# power.net
KiCad netlist of a schematic drawn in Altium Designer
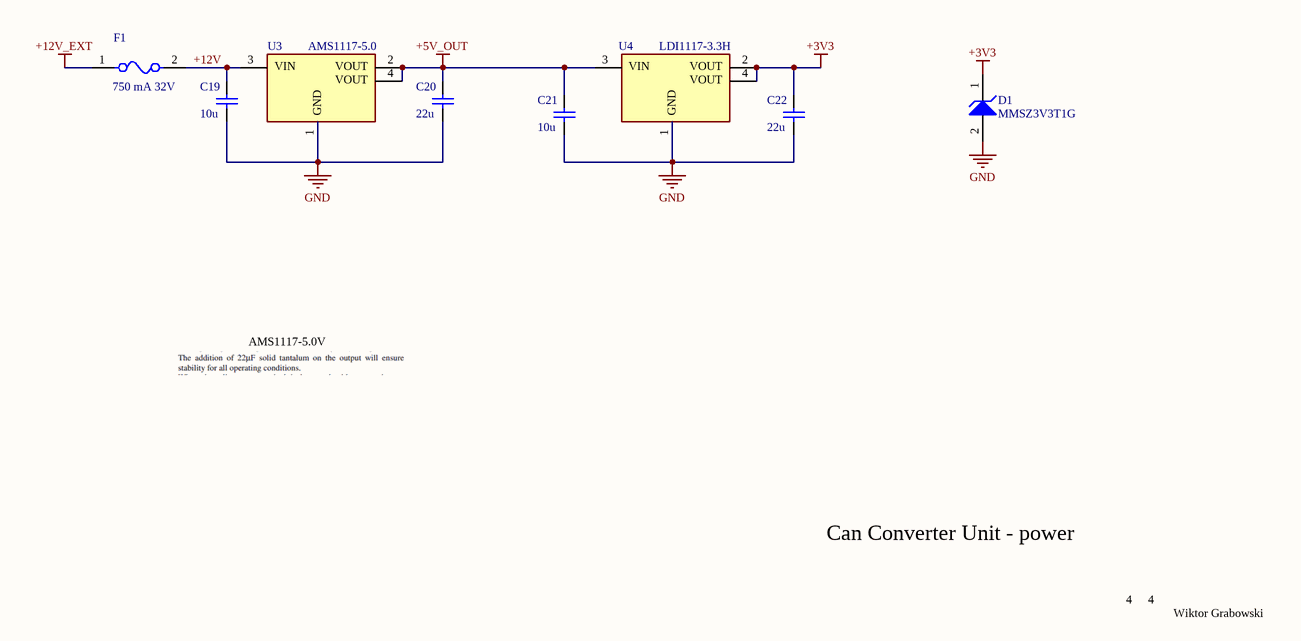
[diagram p0: power.SchDoc]

(export (version "E")
  (design (tool "Eeschema 10.0.6"))
  (components
    (comp (ref "C19")
      (value "10u")
      (footprint "CAPC1206(3216)170_M")
      (description "CAP 47nF 200V ±10% 1206 (3216 Metric) Thickness 1.7mm SMD")
      (fields (field (name "TOLERANCE") "Â±10%"))
      (libsource (lib "Altium Content Vault") (part "CAP"))
    )
    (comp (ref "C20")
      (value "22u")
      (footprint "CAPC1206(3216)170_M")
      (description "CAP 47nF 200V ±10% 1206 (3216 Metric) Thickness 1.7mm SMD")
      (fields (field (name "TOLERANCE") "Â±10%"))
      (libsource (lib "Altium Content Vault") (part "CAP"))
    )
    (comp (ref "C21")
      (value "10u")
      (footprint "CAPC1206(3216)170_M")
      (description "CAP 47nF 200V ±10% 1206 (3216 Metric) Thickness 1.7mm SMD")
      (fields (field (name "TOLERANCE") "Â±10%"))
      (libsource (lib "Altium Content Vault") (part "CAP"))
    )
    (comp (ref "C22")
      (value "22u")
      (footprint "CAPC1206(3216)170_M")
      (description "CAP 47nF 200V ±10% 1206 (3216 Metric) Thickness 1.7mm SMD")
      (fields (field (name "TOLERANCE") "Â±10%"))
      (libsource (lib "Altium Content Vault") (part "CAP"))
    )
    (comp (ref "D1")
      (value "MMSZ3V3T1G")
      (footprint "ONSC-SOD-123-2-425-04_V")
      (description "Zener Voltage Regulator, 500 mW, 2-Pin SOD-123, Pb-Free, Tape and Reel")
      (fields (field (name "MANUFACTURER") "On Semiconductor"))
      (libsource (lib "Altium Content Vault") (part "ONSC-K1A2-2"))
    )
    (comp (ref "F1")
      (value "750 mA 32V")
      (footprint "FP-0466-MFG")
      (description "FUSE BOARD MOUNT 750MA 63VAC/VDC")
      (libsource (lib "Altium Content Vault") (part "5bcf9b9f640e542cf0359d10258e979"))
    )
    (comp (ref "U3")
      (value "AMS1117-5.0")
      (footprint "AMS1117-5.0")
      (description "1A LOW DROPOUT VOLTAGE REGULATOR")
      (libsource (lib "HydrogreenLibrary") (part "AMS1117-5.0"))
    )
    (comp (ref "U4")
      (value "LDI1117-3.3H")
      (footprint "LDI1117-3.3H")
      (description "Fixed Positive LDO Regulator")
      (fields (field (name "MANUFACTURER") "Diotec"))
      (libsource (lib "HydrogreenLibrary") (part "LDI1117-3.3H"))
    )
  )
  (nets
    (net (code "1") (name "+3V3") (class "Default")
      (node (ref "C22") (pin "2") (pinfunction "2_2") (pintype "passive"))
      (node (ref "D1") (pin "1") (pinfunction "K_1") (pintype "passive"))
      (node (ref "U4") (pin "2") (pintype "power_in"))
      (node (ref "U4") (pin "4") (pintype "power_in"))
    )
    (net (code "2") (name "+5V_OUT") (class "Default")
      (node (ref "C20") (pin "2") (pinfunction "2_2") (pintype "passive"))
      (node (ref "C21") (pin "2") (pinfunction "2_2") (pintype "passive"))
      (node (ref "U3") (pin "2") (pintype "power_in"))
      (node (ref "U3") (pin "4") (pintype "power_in"))
      (node (ref "U4") (pin "3") (pintype "power_in"))
    )
    (net (code "3") (name "+12V_EXT") (class "Default")
      (node (ref "F1") (pin "1") (pinfunction "1_1") (pintype "passive"))
    )
    (net (code "4") (name "/+12V") (class "Default")
      (node (ref "C19") (pin "2") (pinfunction "2_2") (pintype "passive"))
      (node (ref "F1") (pin "2") (pinfunction "2_2") (pintype "passive"))
      (node (ref "U3") (pin "3") (pintype "power_in"))
    )
    (net (code "5") (name "GND") (class "Default")
      (node (ref "C19") (pin "1") (pinfunction "1_1") (pintype "passive"))
      (node (ref "C20") (pin "1") (pinfunction "1_1") (pintype "passive"))
      (node (ref "C21") (pin "1") (pinfunction "1_1") (pintype "passive"))
      (node (ref "C22") (pin "1") (pinfunction "1_1") (pintype "passive"))
      (node (ref "D1") (pin "2") (pinfunction "A_2") (pintype "passive"))
      (node (ref "U3") (pin "1") (pintype "passive"))
      (node (ref "U4") (pin "1") (pintype "passive"))
    )
  )
)
